# Single_cell_module.net
KiCad netlist of a schematic drawn in Altium Designer
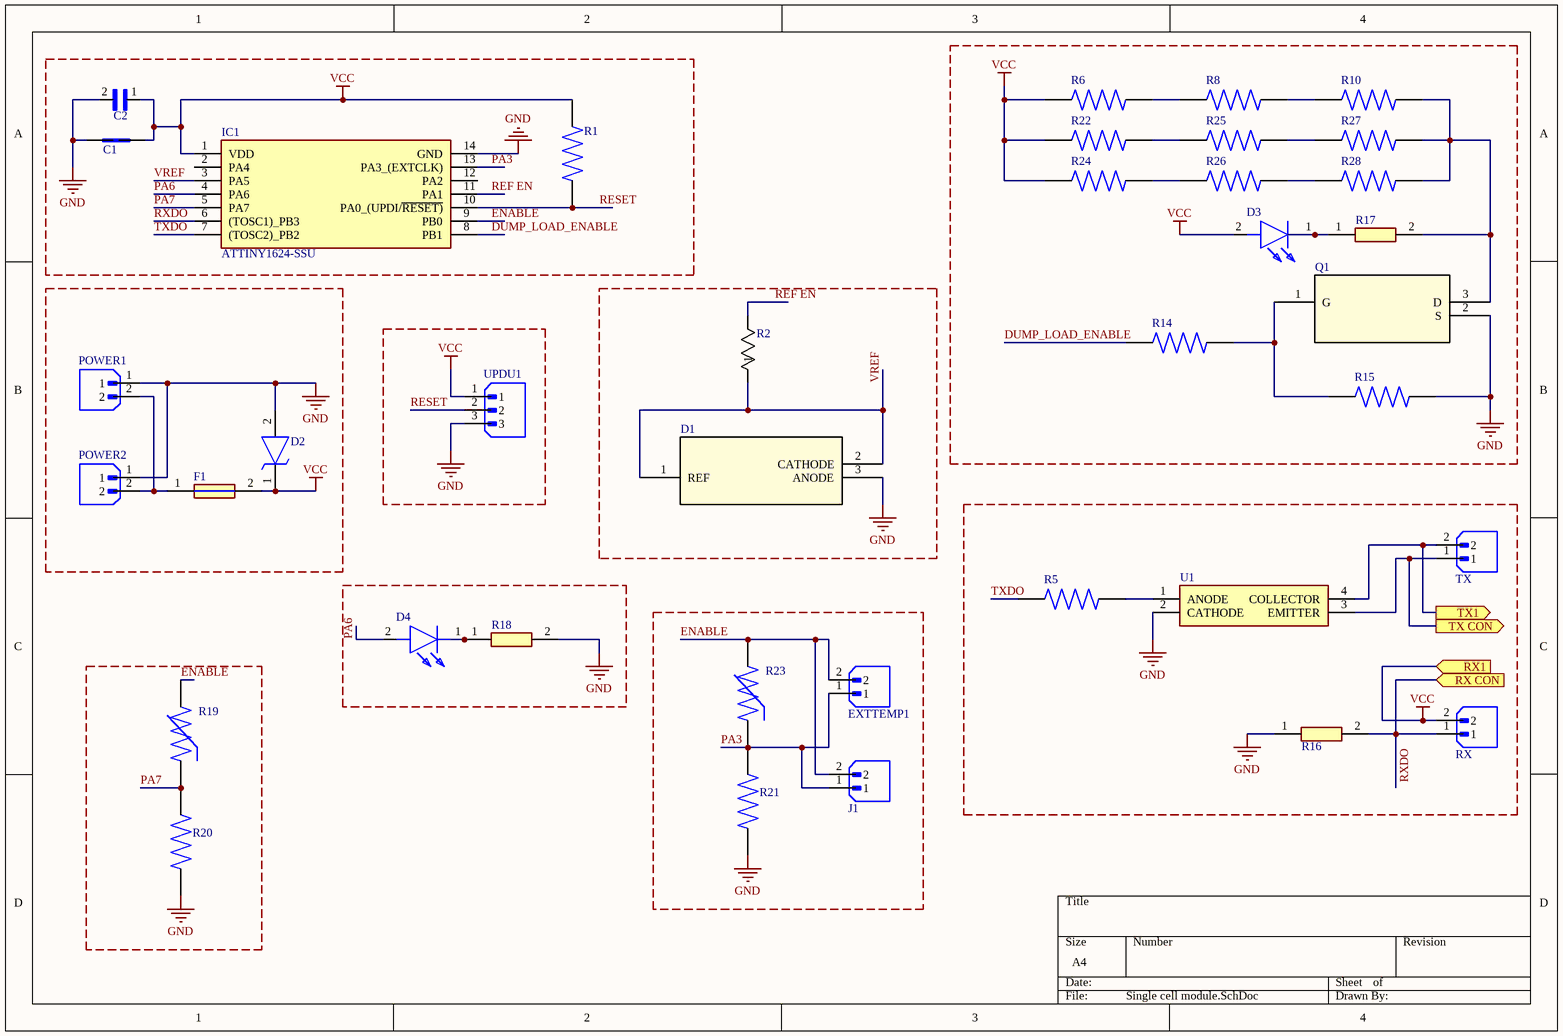
[diagram p0: Single cell module.SchDoc]

(export (version "E")
  (design (tool "Eeschema 10.0.6"))
  (components
    (comp (ref "C1")
      (value "CC0805KRX7R9BB104")
      (footprint "CAPC2012X70")
      (description "0.1ÂµF Â±10% 50V Ceramic Capacitor X7R 0805 _2012 Metric_")
      (fields (field (name "MF") "Yageo"))
      (libsource (lib "CC0805KRX7R9BB104") (part "CC0805KRX7R9BB104"))
    )
    (comp (ref "C2")
      (value "CL21A106KAYNNNE")
      (footprint "CAPC2012X135N")
      (description "10ÂµF Â±10% 25V Ceramic Capacitor X5R 0805 (2012 Metric)")
      (fields (field (name "MF") "Samsung") (field (name "DIGI-KEY_PART_NUMBER") "1276-2891-1-ND"))
      (libsource (lib "CL21A106KAYNNNE") (part "CL21A106KAYNNNE"))
    )
    (comp (ref "D1")
      (value "AZ432ANTR-E1")
      (footprint "SOT-23_DIO")
      (description "No Description Available")
      (libsource (lib "AZ432ANTR-E1") (part "AZ432ANTR-E1"))
    )
    (comp (ref "D2")
      (value "SM6T6V8A")
      (footprint "SamacSys:DIOM5436X265N")
      (description "TVS Diode (Uni-directional)")
      (fields (field (name "MOUSER PART NUMBER") "511-SM6T6V8A"))
      (libsource (lib "*") (part "SM6T6V8A"))
    )
    (comp (ref "D3")
      (value "19-217_GHC-YR1S2_3T")
      (footprint "SamacSys:LEDC1608X50N")
      (description "LED")
      (fields
        (field (name "MANUFACTURER_PART_NUMBER") "19-217/GHC-YR1S2/3T")
        (field (name "MOUSER PART NUMBER") "638-19217GHCYR1S23T")
      )
      (libsource (lib "*") (part "19-217_GHC-YR1S2_3T"))
    )
    (comp (ref "D4")
      (value "19-217_GHC-YR1S2_3T")
      (footprint "SamacSys:LEDC1608X50N")
      (description "LED")
      (fields
        (field (name "MANUFACTURER_PART_NUMBER") "19-217/GHC-YR1S2/3T")
        (field (name "MOUSER PART NUMBER") "638-19217GHCYR1S23T")
      )
      (libsource (lib "*") (part "19-217_GHC-YR1S2_3T"))
    )
    (comp (ref "EXTTEMP1")
      (value "B2B-XH-A(LF)(SN)")
      (footprint "JST_B2B-XH-A(LF)(SN)")
      (description "Connector Header Through Hole 2 position 0.098 (2.50mm)")
      (fields (field (name "MF") "JST Sales America Inc."))
      (libsource (lib "") (part "B2B-XH-A(LF)(SN)_1"))
    )
    (comp (ref "F1")
      (value "MF-MSMF150-2")
      (footprint "SamacSys:FUSC4632X85N")
      (description "Fuse")
      (fields (field (name "MOUSER PART NUMBER") "652-MF-MSMF150-2"))
      (libsource (lib "*") (part "MF-MSMF150-2"))
    )
    (comp (ref "IC1")
      (value "ATTINY1624-SSU")
      (footprint "SamacSys:SOIC127P600X175-14N")
      (description "Integrated Circuit")
      (fields (field (name "MOUSER PART NUMBER") "556-ATTINY1624-SSU"))
      (libsource (lib "*") (part "ATTINY1624-SSU"))
    )
    (comp (ref "J1")
      (value "B2B-XH-A(LF)(SN)")
      (footprint "JST_B2B-XH-A(LF)(SN)")
      (description "Connector Header Through Hole 2 position 0.098 (2.50mm)")
      (fields (field (name "MF") "JST Sales America Inc."))
      (libsource (lib "") (part "B2B-XH-A(LF)(SN)_1"))
    )
    (comp (ref "POWER1")
      (value "B2B-XH-A(LF)(SN)")
      (footprint "JST_B2B-XH-A(LF)(SN)")
      (description "Connector Header Through Hole 2 position 0.098 (2.50mm)")
      (fields (field (name "MF") "JST Sales America Inc."))
      (libsource (lib "B2B-XH-A_LF__SN_") (part "B2B-XH-A(LF)(SN)"))
    )
    (comp (ref "POWER2")
      (value "B2B-XH-A(LF)(SN)")
      (footprint "JST_B2B-XH-A(LF)(SN)")
      (description "Connector Header Through Hole 2 position 0.098 (2.50mm)")
      (fields (field (name "MF") "JST Sales America Inc."))
      (libsource (lib "B2B-XH-A_LF__SN_") (part "B2B-XH-A(LF)(SN)"))
    )
    (comp (ref "Q1")
      (value "AO3400A")
      (footprint "SOT-23-3L_AOS")
      (description "No Description Available")
      (libsource (lib "AO3400A") (part "AO3400A"))
    )
    (comp (ref "R1")
      (value "ERA6ARW104V")
      (footprint "RES_ERA6ARW104V")
      (libsource (lib "ERA6ARW104V") (part "ERA6ARW104V"))
    )
    (comp (ref "R2")
      (value "0805W8F1001T5E")
      (footprint "RES_8F1001T5E_UNR")
      (description "No Description Available")
      (libsource (lib "0805W8F1001T5E") (part "0805W8F1001T5E"))
    )
    (comp (ref "R5")
      (value "ERJ6ENF1800V")
      (footprint "RES_ERJ6ENF1800V")
      (libsource (lib "ERJ6ENF1800V") (part "ERJ6ENF1800V"))
    )
    (comp (ref "R6")
      (value "ERA6ARW104V")
      (footprint "RES_ERA6ARW104V")
      (libsource (lib "ERA6ARW104V") (part "ERA6ARW104V"))
    )
    (comp (ref "R8")
      (value "ERA6ARW104V")
      (footprint "RES_ERA6ARW104V")
      (libsource (lib "ERA6ARW104V") (part "ERA6ARW104V"))
    )
    (comp (ref "R10")
      (value "ERA6ARW104V")
      (footprint "RES_ERA6ARW104V")
      (libsource (lib "ERA6ARW104V") (part "ERA6ARW104V"))
    )
    (comp (ref "R14")
      (value "RT1206DRD07510RL")
      (footprint "RESC3116X65N")
      (description "RES SMD 510 OHM 0.5% 1/8W 1206")
      (libsource (lib "RT1206DRD07510RL") (part "RT1206DRD07510RL"))
    )
    (comp (ref "R15")
      (value "ERJP06D1002V")
      (footprint "RES_ERJP06D1002V")
      (libsource (lib "ERJP06D1002V") (part "ERJP06D1002V"))
    )
    (comp (ref "R16")
      (value "0805W8F2201T5E")
      (footprint "SamacSys:RESC2013X65N")
      (description "Resistor")
      (fields (field (name "MOUSER PART NUMBER") "303-0805W8F2201T5E"))
      (libsource (lib "*") (part "0805W8F2201T5E"))
    )
    (comp (ref "R17")
      (value "0805W8F2201T5E")
      (footprint "SamacSys:RESC2013X65N")
      (description "Resistor")
      (fields (field (name "MOUSER PART NUMBER") "303-0805W8F2201T5E"))
      (libsource (lib "*") (part "0805W8F2201T5E"))
    )
    (comp (ref "R18")
      (value "0805W8F2201T5E")
      (footprint "SamacSys:RESC2013X65N")
      (description "Resistor")
      (fields (field (name "MOUSER PART NUMBER") "303-0805W8F2201T5E"))
      (libsource (lib "*") (part "0805W8F2201T5E"))
    )
    (comp (ref "R19")
      (value "NCP18WF104J03RB")
      (footprint "THRMC1608X95N")
      (description "NTC Thermistor 100k 0603 (1608 Metric)")
      (fields (field (name "MF") "Murata Electronics"))
      (libsource (lib "NCP18WF104J03RB") (part "NCP18WF104J03RB"))
    )
    (comp (ref "R20")
      (value "ERJP06D1002V")
      (footprint "RES_ERJP06D1002V")
      (libsource (lib "ERJP06D1002V") (part "ERJP06D1002V"))
    )
    (comp (ref "R21")
      (value "ERJP06D1002V")
      (footprint "RES_ERJP06D1002V")
      (libsource (lib "ERJP06D1002V") (part "ERJP06D1002V"))
    )
    (comp (ref "R22")
      (value "ERA6ARW104V")
      (footprint "RES_ERA6ARW104V")
      (libsource (lib "ERA6ARW104V") (part "ERA6ARW104V"))
    )
    (comp (ref "R23")
      (value "NCP18WF104J03RB")
      (footprint "THRMC1608X95N")
      (description "NTC Thermistor 100k 0603 (1608 Metric)")
      (fields (field (name "MF") "Murata Electronics"))
      (libsource (lib "NCP18WF104J03RB") (part "NCP18WF104J03RB"))
    )
    (comp (ref "R24")
      (value "ERA6ARW104V")
      (footprint "RES_ERA6ARW104V")
      (libsource (lib "ERA6ARW104V") (part "ERA6ARW104V"))
    )
    (comp (ref "R25")
      (value "ERA6ARW104V")
      (footprint "RES_ERA6ARW104V")
      (libsource (lib "ERA6ARW104V") (part "ERA6ARW104V"))
    )
    (comp (ref "R26")
      (value "ERA6ARW104V")
      (footprint "RES_ERA6ARW104V")
      (libsource (lib "ERA6ARW104V") (part "ERA6ARW104V"))
    )
    (comp (ref "R27")
      (value "ERA6ARW104V")
      (footprint "RES_ERA6ARW104V")
      (libsource (lib "ERA6ARW104V") (part "ERA6ARW104V"))
    )
    (comp (ref "R28")
      (value "ERA6ARW104V")
      (footprint "RES_ERA6ARW104V")
      (libsource (lib "ERA6ARW104V") (part "ERA6ARW104V"))
    )
    (comp (ref "RX")
      (value "B2B-XH-A(LF)(SN)")
      (footprint "JST_B2B-XH-A(LF)(SN)")
      (description "Connector Header Through Hole 2 position 0.098 (2.50mm)")
      (fields (field (name "MF") "JST Sales America Inc."))
      (libsource (lib "") (part "B2B-XH-A(LF)(SN)_1"))
    )
    (comp (ref "TX")
      (value "B2B-XH-A(LF)(SN)")
      (footprint "JST_B2B-XH-A(LF)(SN)")
      (description "Connector Header Through Hole 2 position 0.098 (2.50mm)")
      (fields (field (name "MF") "JST Sales America Inc."))
      (libsource (lib "") (part "B2B-XH-A(LF)(SN)_1"))
    )
    (comp (ref "U1")
      (value "EL3H7_B__TA_-G")
      (footprint "SamacSys:SOIC127P700X200-4N")
      (description "Integrated Circuit")
      (fields
        (field (name "MANUFACTURER_PART_NUMBER") "EL3H7(B)(TA)-G")
        (field (name "MOUSER PART NUMBER") "638-EL3H7BTAG")
      )
      (libsource (lib "*") (part "EL3H7_B__TA_-G"))
    )
    (comp (ref "UPDU1")
      (value "B3B-XH-A_(LF)(SN)")
      (footprint "JST_B3B-XH-A (LF)(SN)")
      (description "Connector Header Through Hole 3 position 0.098 (2.50mm)")
      (fields (field (name "MF") "JST Sales America Inc.") (field (name "MP") "B3B-XH-A (LF)(SN)"))
      (libsource (lib "B3B-XH-A__LF__SN_") (part "B3B-XH-A_(LF)(SN)"))
    )
  )
  (nets
    (net (code "1") (name "/DUMP_LOAD_ENABLE") (class "Default")
      (node (ref "IC1") (pin "8") (pinfunction "PB1_8") (pintype "passive"))
      (node (ref "R14") (pin "1") (pinfunction "1_1") (pintype "passive"))
    )
    (net (code "2") (name "/ENABLE") (class "Default")
      (node (ref "EXTTEMP1") (pin "2") (pinfunction "2_2") (pintype "passive"))
      (node (ref "IC1") (pin "9") (pinfunction "PB0_9") (pintype "passive"))
      (node (ref "J1") (pin "2") (pinfunction "2_2") (pintype "passive"))
      (node (ref "R19") (pin "2") (pinfunction "2_2") (pintype "passive"))
      (node (ref "R23") (pin "2") (pinfunction "2_2") (pintype "passive"))
    )
    (net (code "3") (name "/PA3") (class "Default")
      (node (ref "EXTTEMP1") (pin "1") (pinfunction "1_1") (pintype "passive"))
      (node (ref "IC1") (pin "13") (pinfunction "PA3_(EXTCLK)_13") (pintype "passive"))
      (node (ref "J1") (pin "1") (pinfunction "1_1") (pintype "passive"))
      (node (ref "R21") (pin "2") (pinfunction "2_2") (pintype "passive"))
      (node (ref "R23") (pin "1") (pinfunction "1_1") (pintype "passive"))
    )
    (net (code "4") (name "/PA6") (class "Default")
      (node (ref "D4") (pin "2") (pinfunction "A_2") (pintype "passive"))
      (node (ref "IC1") (pin "4") (pinfunction "PA6_4") (pintype "passive"))
    )
    (net (code "5") (name "/PA7") (class "Default")
      (node (ref "IC1") (pin "5") (pinfunction "PA7_5") (pintype "passive"))
      (node (ref "R19") (pin "1") (pinfunction "1_1") (pintype "passive"))
      (node (ref "R20") (pin "2") (pinfunction "2_2") (pintype "passive"))
    )
    (net (code "6") (name "/REF EN") (class "Default")
      (node (ref "IC1") (pin "11") (pinfunction "PA1_11") (pintype "passive"))
      (node (ref "R2") (pin "2") (pinfunction "2_2") (pintype "passive"))
    )
    (net (code "7") (name "/RESET") (class "Default")
      (node (ref "IC1") (pin "10") (pinfunction "PA0_(UPDI/~{RESET)}_10") (pintype "passive"))
      (node (ref "R1") (pin "1") (pinfunction "1_1") (pintype "passive"))
      (node (ref "UPDU1") (pin "2") (pinfunction "2_2") (pintype "passive"))
    )
    (net (code "8") (name "/RXDO") (class "Default")
      (node (ref "IC1") (pin "6") (pinfunction "(TOSC1)_PB3_6") (pintype "passive"))
      (node (ref "R16") (pin "2") (pinfunction "2_2") (pintype "passive"))
      (node (ref "RX") (pin "1") (pinfunction "1_1") (pintype "passive"))
    )
    (net (code "9") (name "/TX CON") (class "Default")
      (node (ref "TX") (pin "1") (pinfunction "1_1") (pintype "passive"))
      (node (ref "U1") (pin "3") (pinfunction "EMITTER_3") (pintype "passive"))
    )
    (net (code "10") (name "/TX1") (class "Default")
      (node (ref "TX") (pin "2") (pinfunction "2_2") (pintype "passive"))
      (node (ref "U1") (pin "4") (pinfunction "COLLECTOR_4") (pintype "passive"))
    )
    (net (code "11") (name "/TXDO") (class "Default")
      (node (ref "IC1") (pin "7") (pinfunction "(TOSC2)_PB2_7") (pintype "passive"))
      (node (ref "R5") (pin "1") (pinfunction "1_1") (pintype "passive"))
    )
    (net (code "12") (name "/VREF") (class "Default")
      (node (ref "D1") (pin "1") (pinfunction "REF_1") (pintype "passive"))
      (node (ref "D1") (pin "2") (pinfunction "CATHODE_2") (pintype "passive"))
      (node (ref "IC1") (pin "3") (pinfunction "PA5_3") (pintype "passive"))
      (node (ref "R2") (pin "1") (pinfunction "1_1") (pintype "passive"))
    )
    (net (code "13") (name "GND") (class "Default")
      (node (ref "C1") (pin "1") (pinfunction "1_1") (pintype "passive"))
      (node (ref "C2") (pin "2") (pinfunction "2_2") (pintype "passive"))
      (node (ref "D1") (pin "3") (pinfunction "ANODE_3") (pintype "passive"))
      (node (ref "D2") (pin "2") (pinfunction "A_2") (pintype "passive"))
      (node (ref "IC1") (pin "14") (pinfunction "GND_14") (pintype "passive"))
      (node (ref "POWER1") (pin "1") (pinfunction "1_1") (pintype "passive"))
      (node (ref "POWER2") (pin "1") (pinfunction "1_1") (pintype "passive"))
      (node (ref "Q1") (pin "2") (pinfunction "S_2") (pintype "passive"))
      (node (ref "R15") (pin "2") (pinfunction "2_2") (pintype "passive"))
      (node (ref "R16") (pin "1") (pinfunction "1_1") (pintype "passive"))
      (node (ref "R18") (pin "2") (pinfunction "2_2") (pintype "passive"))
      (node (ref "R20") (pin "1") (pinfunction "1_1") (pintype "passive"))
      (node (ref "R21") (pin "1") (pinfunction "1_1") (pintype "passive"))
      (node (ref "U1") (pin "2") (pinfunction "CATHODE_2") (pintype "passive"))
      (node (ref "UPDU1") (pin "3") (pinfunction "3_3") (pintype "passive"))
    )
    (net (code "14") (name "Net-(D3-K)") (class "Default")
      (node (ref "D3") (pin "1") (pinfunction "K_1") (pintype "passive"))
      (node (ref "R17") (pin "1") (pinfunction "1_1") (pintype "passive"))
    )
    (net (code "15") (name "Net-(D4-K)") (class "Default")
      (node (ref "D4") (pin "1") (pinfunction "K_1") (pintype "passive"))
      (node (ref "R18") (pin "1") (pinfunction "1_1") (pintype "passive"))
    )
    (net (code "16") (name "Net-(F1-Pad1)") (class "Default")
      (node (ref "F1") (pin "1") (pinfunction "1_1") (pintype "passive"))
      (node (ref "POWER1") (pin "2") (pinfunction "2_2") (pintype "passive"))
      (node (ref "POWER2") (pin "2") (pinfunction "2_2") (pintype "passive"))
    )
    (net (code "17") (name "Net-(Q1-D)") (class "Default")
      (node (ref "Q1") (pin "3") (pinfunction "D_3") (pintype "passive"))
      (node (ref "R10") (pin "2") (pinfunction "2_2") (pintype "passive"))
      (node (ref "R17") (pin "2") (pinfunction "2_2") (pintype "passive"))
      (node (ref "R27") (pin "2") (pinfunction "2_2") (pintype "passive"))
      (node (ref "R28") (pin "2") (pinfunction "2_2") (pintype "passive"))
    )
    (net (code "18") (name "Net-(Q1-G)") (class "Default")
      (node (ref "Q1") (pin "1") (pinfunction "G_1") (pintype "passive"))
      (node (ref "R14") (pin "2") (pinfunction "2_2") (pintype "passive"))
      (node (ref "R15") (pin "1") (pinfunction "1_1") (pintype "passive"))
    )
    (net (code "19") (name "Net-(R6-Pad2)") (class "Default")
      (node (ref "R6") (pin "2") (pinfunction "2_2") (pintype "passive"))
      (node (ref "R8") (pin "1") (pinfunction "1_1") (pintype "passive"))
    )
    (net (code "20") (name "Net-(R10-Pad1)") (class "Default")
      (node (ref "R10") (pin "1") (pinfunction "1_1") (pintype "passive"))
      (node (ref "R8") (pin "2") (pinfunction "2_2") (pintype "passive"))
    )
    (net (code "21") (name "Net-(R22-Pad2)") (class "Default")
      (node (ref "R22") (pin "2") (pinfunction "2_2") (pintype "passive"))
      (node (ref "R25") (pin "1") (pinfunction "1_1") (pintype "passive"))
    )
    (net (code "22") (name "Net-(R24-Pad2)") (class "Default")
      (node (ref "R24") (pin "2") (pinfunction "2_2") (pintype "passive"))
      (node (ref "R26") (pin "1") (pinfunction "1_1") (pintype "passive"))
    )
    (net (code "23") (name "Net-(R25-Pad2)") (class "Default")
      (node (ref "R25") (pin "2") (pinfunction "2_2") (pintype "passive"))
      (node (ref "R27") (pin "1") (pinfunction "1_1") (pintype "passive"))
    )
    (net (code "24") (name "Net-(R26-Pad2)") (class "Default")
      (node (ref "R26") (pin "2") (pinfunction "2_2") (pintype "passive"))
      (node (ref "R28") (pin "1") (pinfunction "1_1") (pintype "passive"))
    )
    (net (code "25") (name "Net-(U1-ANODE)") (class "Default")
      (node (ref "R5") (pin "2") (pinfunction "2_2") (pintype "passive"))
      (node (ref "U1") (pin "1") (pinfunction "ANODE_1") (pintype "passive"))
    )
    (net (code "26") (name "VCC") (class "Default")
      (node (ref "C1") (pin "2") (pinfunction "2_2") (pintype "passive"))
      (node (ref "C2") (pin "1") (pinfunction "1_1") (pintype "passive"))
      (node (ref "D2") (pin "1") (pinfunction "K_1") (pintype "passive"))
      (node (ref "D3") (pin "2") (pinfunction "A_2") (pintype "passive"))
      (node (ref "F1") (pin "2") (pinfunction "2_2") (pintype "passive"))
      (node (ref "IC1") (pin "1") (pinfunction "VDD_1") (pintype "passive"))
      (node (ref "R1") (pin "2") (pinfunction "2_2") (pintype "passive"))
      (node (ref "R22") (pin "1") (pinfunction "1_1") (pintype "passive"))
      (node (ref "R24") (pin "1") (pinfunction "1_1") (pintype "passive"))
      (node (ref "R6") (pin "1") (pinfunction "1_1") (pintype "passive"))
      (node (ref "RX") (pin "2") (pinfunction "2_2") (pintype "passive"))
      (node (ref "UPDU1") (pin "1") (pinfunction "1_1") (pintype "passive"))
    )
    (net (code "27") (name "unconnected-(IC1-PA2-Pad12)") (class "Default")
      (node (ref "IC1") (pin "12") (pinfunction "PA2_12") (pintype "passive"))
    )
    (net (code "28") (name "unconnected-(IC1-PA4-Pad2)") (class "Default")
      (node (ref "IC1") (pin "2") (pinfunction "PA4_2") (pintype "passive"))
    )
  )
)
